# dual_power_supply.net
KiCad netlist of a schematic drawn in EAGLE
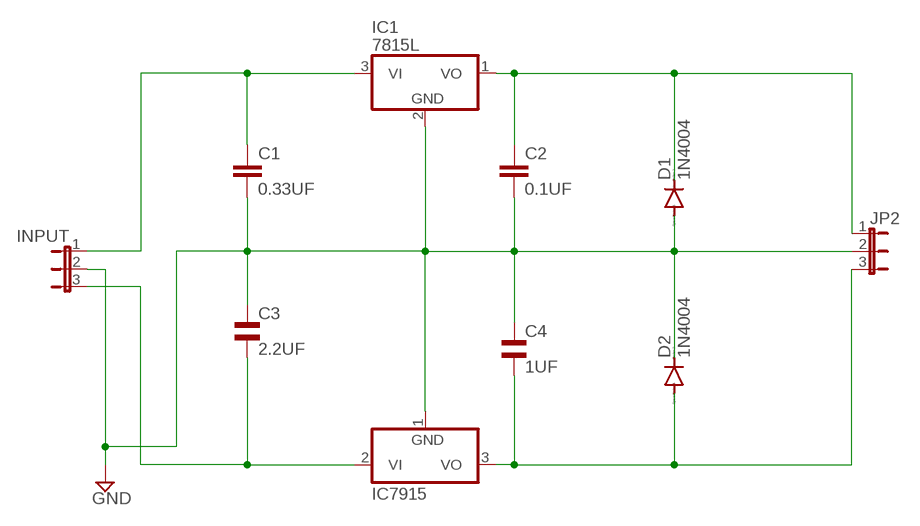
[diagram p0: schematic, sheet 1]

(export (version "E")
  (design (tool "Eeschema 10.0.6"))
  (components
    (comp (ref "C1")
      (value "0.33UF")
      (footprint "eagle-import:C2.5-2")
      (libsource (lib "eagle-import") (part "C2.5/2"))
    )
    (comp (ref "C2")
      (value "0.1UF")
      (footprint "eagle-import:C2.5-2")
      (libsource (lib "eagle-import") (part "C2.5/2"))
    )
    (comp (ref "C3")
      (value "2.2UF")
      (footprint "eagle-import:EU25-10")
      (libsource (lib "eagle-import") (part "EL-BI25-10AXIAL"))
    )
    (comp (ref "C4")
      (value "1UF")
      (footprint "eagle-import:EU25-10")
      (libsource (lib "eagle-import") (part "EL-BI25-10AXIAL"))
    )
    (comp (ref "D1")
      (value "1N4004")
      (footprint "eagle-import:DO41-10")
      (libsource (lib "eagle-import") (part "1N4004"))
    )
    (comp (ref "D2")
      (value "1N4004")
      (footprint "eagle-import:DO41-10")
      (libsource (lib "eagle-import") (part "1N4004"))
    )
    (comp (ref "IC1")
      (value "7815L")
      (footprint "eagle-import:TO92")
      (libsource (lib "eagle-import") (part "78L15"))
    )
    (comp (ref "IC7915")
      (value "7915L")
      (footprint "eagle-import:TO92")
      (libsource (lib "eagle-import") (part "79L15"))
    )
    (comp (ref "INPUT")
      (value "JP2E")
      (footprint "eagle-import:JP2")
      (libsource (lib "eagle-import") (part "JP2E"))
    )
    (comp (ref "JP2")
      (value "JP2E")
      (footprint "eagle-import:JP2")
      (libsource (lib "eagle-import") (part "JP2E"))
    )
  )
  (nets
    (net (code "1") (name "GND") (class "Default")
      (node (ref "C1") (pin "2") (pinfunction "2_2") (pintype "passive"))
      (node (ref "C2") (pin "2") (pinfunction "2_2") (pintype "passive"))
      (node (ref "C3") (pin "1") (pinfunction "1_1") (pintype "passive"))
      (node (ref "C4") (pin "1") (pinfunction "1_1") (pintype "passive"))
      (node (ref "D1") (pin "A") (pinfunction "A_A") (pintype "passive"))
      (node (ref "D2") (pin "C") (pinfunction "C_C") (pintype "passive"))
      (node (ref "IC1") (pin "2") (pinfunction "GND_2") (pintype "passive"))
      (node (ref "IC7915") (pin "1") (pinfunction "GND_1") (pintype "passive"))
      (node (ref "INPUT") (pin "2") (pinfunction "2_2") (pintype "passive"))
      (node (ref "JP2") (pin "2") (pinfunction "2_2") (pintype "passive"))
    )
    (net (code "2") (name "Net-(IC1-VI)") (class "Default")
      (node (ref "C1") (pin "1") (pinfunction "1_1") (pintype "passive"))
      (node (ref "IC1") (pin "3") (pinfunction "VI_3") (pintype "input"))
      (node (ref "INPUT") (pin "1") (pinfunction "1_1") (pintype "passive"))
    )
    (net (code "3") (name "Net-(IC1-VO)") (class "Default")
      (node (ref "C2") (pin "1") (pinfunction "1_1") (pintype "passive"))
      (node (ref "D1") (pin "C") (pinfunction "C_C") (pintype "passive"))
      (node (ref "IC1") (pin "1") (pinfunction "VO_1") (pintype "passive"))
      (node (ref "JP2") (pin "1") (pinfunction "1_1") (pintype "passive"))
    )
    (net (code "4") (name "Net-(IC7915-VI)") (class "Default")
      (node (ref "C3") (pin "2") (pinfunction "2_2") (pintype "passive"))
      (node (ref "IC7915") (pin "2") (pinfunction "VI_2") (pintype "input"))
      (node (ref "INPUT") (pin "3") (pinfunction "3_3") (pintype "passive"))
    )
    (net (code "5") (name "Net-(IC7915-VO)") (class "Default")
      (node (ref "C4") (pin "2") (pinfunction "2_2") (pintype "passive"))
      (node (ref "D2") (pin "A") (pinfunction "A_A") (pintype "passive"))
      (node (ref "IC7915") (pin "3") (pinfunction "VO_3") (pintype "passive"))
      (node (ref "JP2") (pin "3") (pinfunction "3_3") (pintype "passive"))
    )
  )
)
